# three_led_breakout.net
KiCad netlist of a schematic drawn in EAGLE
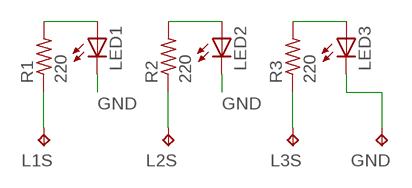
[diagram p0: schematic, sheet 1]

(export (version "E")
  (design (tool "Eeschema 10.0.6"))
  (components
    (comp (ref "GND")
      (value "TPTP13SQ")
      (footprint "eagle-import:TP13SQ")
      (libsource (lib "eagle-import") (part "TPTP13SQ"))
    )
    (comp (ref "L1S")
      (value "TPTP13R")
      (footprint "eagle-import:TP13R")
      (libsource (lib "eagle-import") (part "TPTP13R"))
    )
    (comp (ref "L2S")
      (value "TPTP13R")
      (footprint "eagle-import:TP13R")
      (libsource (lib "eagle-import") (part "TPTP13R"))
    )
    (comp (ref "L3S")
      (value "TPTP13R")
      (footprint "eagle-import:TP13R")
      (libsource (lib "eagle-import") (part "TPTP13R"))
    )
    (comp (ref "LED1")
      (value "LEDSML0603")
      (footprint "eagle-import:SML0603")
      (libsource (lib "eagle-import") (part "LEDSML0603"))
    )
    (comp (ref "LED2")
      (value "LEDSML0603")
      (footprint "eagle-import:SML0603")
      (libsource (lib "eagle-import") (part "LEDSML0603"))
    )
    (comp (ref "LED3")
      (value "LEDSML0603")
      (footprint "eagle-import:SML0603")
      (libsource (lib "eagle-import") (part "LEDSML0603"))
    )
    (comp (ref "R1")
      (value "220")
      (footprint "eagle-import:R0603")
      (libsource (lib "eagle-import") (part "R-US_R0603"))
    )
    (comp (ref "R2")
      (value "220")
      (footprint "eagle-import:R0603")
      (libsource (lib "eagle-import") (part "R-US_R0603"))
    )
    (comp (ref "R3")
      (value "220")
      (footprint "eagle-import:R0603")
      (libsource (lib "eagle-import") (part "R-US_R0603"))
    )
  )
  (nets
    (net (code "1") (name "/GND") (class "Default")
      (node (ref "GND") (pin "TP") (pinfunction "TP_TP") (pintype "input"))
      (node (ref "LED1") (pin "C") (pinfunction "C_C") (pintype "passive"))
      (node (ref "LED2") (pin "C") (pinfunction "C_C") (pintype "passive"))
      (node (ref "LED3") (pin "C") (pinfunction "C_C") (pintype "passive"))
    )
    (net (code "2") (name "Net-(L1S-PadTP)") (class "Default")
      (node (ref "L1S") (pin "TP") (pinfunction "TP_TP") (pintype "input"))
      (node (ref "R1") (pin "1") (pinfunction "1_1") (pintype "passive"))
    )
    (net (code "3") (name "Net-(L2S-PadTP)") (class "Default")
      (node (ref "L2S") (pin "TP") (pinfunction "TP_TP") (pintype "input"))
      (node (ref "R2") (pin "1") (pinfunction "1_1") (pintype "passive"))
    )
    (net (code "4") (name "Net-(L3S-PadTP)") (class "Default")
      (node (ref "L3S") (pin "TP") (pinfunction "TP_TP") (pintype "input"))
      (node (ref "R3") (pin "1") (pinfunction "1_1") (pintype "passive"))
    )
    (net (code "5") (name "Net-(LED1-PadA)") (class "Default")
      (node (ref "LED1") (pin "A") (pinfunction "A_A") (pintype "passive"))
      (node (ref "R1") (pin "2") (pinfunction "2_2") (pintype "passive"))
    )
    (net (code "6") (name "Net-(LED2-PadA)") (class "Default")
      (node (ref "LED2") (pin "A") (pinfunction "A_A") (pintype "passive"))
      (node (ref "R2") (pin "2") (pinfunction "2_2") (pintype "passive"))
    )
    (net (code "7") (name "Net-(LED3-PadA)") (class "Default")
      (node (ref "LED3") (pin "A") (pinfunction "A_A") (pintype "passive"))
      (node (ref "R3") (pin "2") (pinfunction "2_2") (pintype "passive"))
    )
  )
)
